# RN4020C-1C.net
KiCad netlist of a schematic drawn in EAGLE
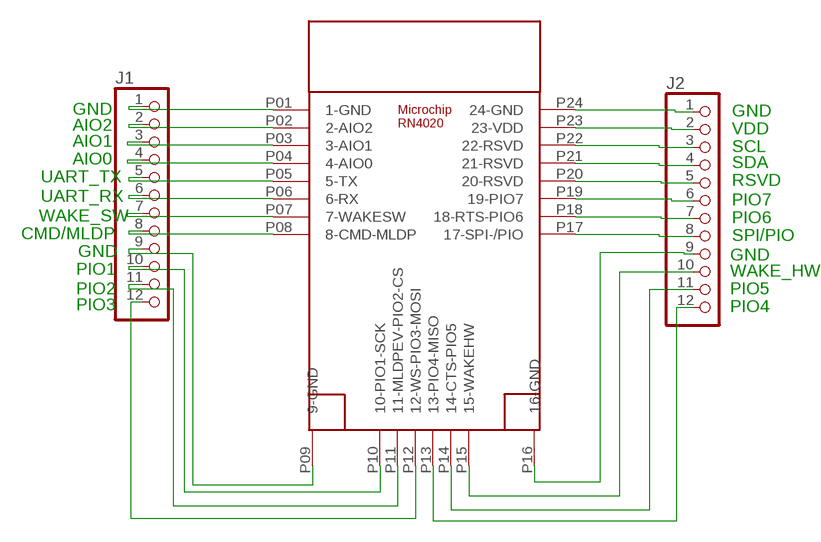
[diagram p0: schematic, sheet 1]

(export (version "E")
  (design (tool "Eeschema 10.0.6"))
  (components
    (comp (ref "J1")
      (value "PINHD-1X12")
      (footprint "eagle-import:1X12")
      (libsource (lib "eagle-import") (part "PINHD-1X12"))
    )
    (comp (ref "J2")
      (value "PINHD-1X12")
      (footprint "eagle-import:1X12")
      (libsource (lib "eagle-import") (part "PINHD-1X12"))
    )
    (comp (ref "U$2")
      (value "RN4020")
      (footprint "eagle-import:RN4020SMD")
      (libsource (lib "eagle-import") (part "RN4020"))
    )
  )
  (nets
    (net (code "1") (name "Net-(U$2-1-GND)") (class "Default")
      (node (ref "J1") (pin "1") (pinfunction "1_1") (pintype "passive"))
      (node (ref "U$2") (pin "P01") (pinfunction "1-GND_P01") (pintype "bidirectional"))
    )
    (net (code "2") (name "Net-(U$2-2-AIO2)") (class "Default")
      (node (ref "J1") (pin "2") (pinfunction "2_2") (pintype "passive"))
      (node (ref "U$2") (pin "P02") (pinfunction "2-AIO2_P02") (pintype "bidirectional"))
    )
    (net (code "3") (name "Net-(U$2-3-AIO1)") (class "Default")
      (node (ref "J1") (pin "3") (pinfunction "3_3") (pintype "passive"))
      (node (ref "U$2") (pin "P03") (pinfunction "3-AIO1_P03") (pintype "bidirectional"))
    )
    (net (code "4") (name "Net-(U$2-4-AIO0)") (class "Default")
      (node (ref "J1") (pin "4") (pinfunction "4_4") (pintype "passive"))
      (node (ref "U$2") (pin "P04") (pinfunction "4-AIO0_P04") (pintype "bidirectional"))
    )
    (net (code "5") (name "Net-(U$2-5-TX)") (class "Default")
      (node (ref "J1") (pin "5") (pinfunction "5_5") (pintype "passive"))
      (node (ref "U$2") (pin "P05") (pinfunction "5-TX_P05") (pintype "bidirectional"))
    )
    (net (code "6") (name "Net-(U$2-6-RX)") (class "Default")
      (node (ref "J1") (pin "6") (pinfunction "6_6") (pintype "passive"))
      (node (ref "U$2") (pin "P06") (pinfunction "6-RX_P06") (pintype "bidirectional"))
    )
    (net (code "7") (name "Net-(U$2-7-WAKESW)") (class "Default")
      (node (ref "J1") (pin "7") (pinfunction "7_7") (pintype "passive"))
      (node (ref "U$2") (pin "P07") (pinfunction "7-WAKESW_P07") (pintype "bidirectional"))
    )
    (net (code "8") (name "Net-(U$2-8-CMD-MLDP)") (class "Default")
      (node (ref "J1") (pin "8") (pinfunction "8_8") (pintype "passive"))
      (node (ref "U$2") (pin "P08") (pinfunction "8-CMD-MLDP_P08") (pintype "bidirectional"))
    )
    (net (code "9") (name "Net-(U$2-9-GND)") (class "Default")
      (node (ref "J1") (pin "9") (pinfunction "9_9") (pintype "passive"))
      (node (ref "U$2") (pin "P09") (pinfunction "9-GND_P09") (pintype "bidirectional"))
    )
    (net (code "10") (name "Net-(U$2-10-PIO1-SCK)") (class "Default")
      (node (ref "J1") (pin "10") (pinfunction "10_10") (pintype "passive"))
      (node (ref "U$2") (pin "P10") (pinfunction "10-PIO1-SCK_P10") (pintype "bidirectional"))
    )
    (net (code "11") (name "Net-(U$2-11-MLDPEV-PIO2-CS)") (class "Default")
      (node (ref "J1") (pin "11") (pinfunction "11_11") (pintype "passive"))
      (node (ref "U$2") (pin "P11") (pinfunction "11-MLDPEV-PIO2-CS_P11") (pintype "bidirectional"))
    )
    (net (code "12") (name "Net-(U$2-12-WS-PIO3-MOSI)") (class "Default")
      (node (ref "J1") (pin "12") (pinfunction "12_12") (pintype "passive"))
      (node (ref "U$2") (pin "P12") (pinfunction "12-WS-PIO3-MOSI_P12") (pintype "bidirectional"))
    )
    (net (code "13") (name "Net-(U$2-13-PIO4-MISO)") (class "Default")
      (node (ref "J2") (pin "12") (pinfunction "12_12") (pintype "passive"))
      (node (ref "U$2") (pin "P13") (pinfunction "13-PIO4-MISO_P13") (pintype "bidirectional"))
    )
    (net (code "14") (name "Net-(U$2-14-CTS-PIO5)") (class "Default")
      (node (ref "J2") (pin "11") (pinfunction "11_11") (pintype "passive"))
      (node (ref "U$2") (pin "P14") (pinfunction "14-CTS-PIO5_P14") (pintype "bidirectional"))
    )
    (net (code "15") (name "Net-(U$2-15-WAKEHW)") (class "Default")
      (node (ref "J2") (pin "10") (pinfunction "10_10") (pintype "passive"))
      (node (ref "U$2") (pin "P15") (pinfunction "15-WAKEHW_P15") (pintype "bidirectional"))
    )
    (net (code "16") (name "Net-(U$2-16-GND)") (class "Default")
      (node (ref "J2") (pin "9") (pinfunction "9_9") (pintype "passive"))
      (node (ref "U$2") (pin "P16") (pinfunction "16-GND_P16") (pintype "bidirectional"))
    )
    (net (code "17") (name "Net-(U$2-17-SPI-{slash}PIO)") (class "Default")
      (node (ref "J2") (pin "8") (pinfunction "8_8") (pintype "passive"))
      (node (ref "U$2") (pin "P17") (pinfunction "17-SPI-/PIO_P17") (pintype "bidirectional"))
    )
    (net (code "18") (name "Net-(U$2-18-RTS-PIO6)") (class "Default")
      (node (ref "J2") (pin "7") (pinfunction "7_7") (pintype "passive"))
      (node (ref "U$2") (pin "P18") (pinfunction "18-RTS-PIO6_P18") (pintype "bidirectional"))
    )
    (net (code "19") (name "Net-(U$2-19-PIO7)") (class "Default")
      (node (ref "J2") (pin "6") (pinfunction "6_6") (pintype "passive"))
      (node (ref "U$2") (pin "P19") (pinfunction "19-PIO7_P19") (pintype "bidirectional"))
    )
    (net (code "20") (name "Net-(U$2-20-RSVD)") (class "Default")
      (node (ref "J2") (pin "5") (pinfunction "5_5") (pintype "passive"))
      (node (ref "U$2") (pin "P20") (pinfunction "20-RSVD_P20") (pintype "bidirectional"))
    )
    (net (code "21") (name "Net-(U$2-21-RSVD)") (class "Default")
      (node (ref "J2") (pin "4") (pinfunction "4_4") (pintype "passive"))
      (node (ref "U$2") (pin "P21") (pinfunction "21-RSVD_P21") (pintype "bidirectional"))
    )
    (net (code "22") (name "Net-(U$2-22-RSVD)") (class "Default")
      (node (ref "J2") (pin "3") (pinfunction "3_3") (pintype "passive"))
      (node (ref "U$2") (pin "P22") (pinfunction "22-RSVD_P22") (pintype "bidirectional"))
    )
    (net (code "23") (name "Net-(U$2-23-VDD)") (class "Default")
      (node (ref "J2") (pin "2") (pinfunction "2_2") (pintype "passive"))
      (node (ref "U$2") (pin "P23") (pinfunction "23-VDD_P23") (pintype "bidirectional"))
    )
    (net (code "24") (name "Net-(U$2-24-GND)") (class "Default")
      (node (ref "J2") (pin "1") (pinfunction "1_1") (pintype "passive"))
      (node (ref "U$2") (pin "P24") (pinfunction "24-GND_P24") (pintype "bidirectional"))
    )
  )
)
